# project.net
KiCad netlist of a schematic drawn in EAGLE
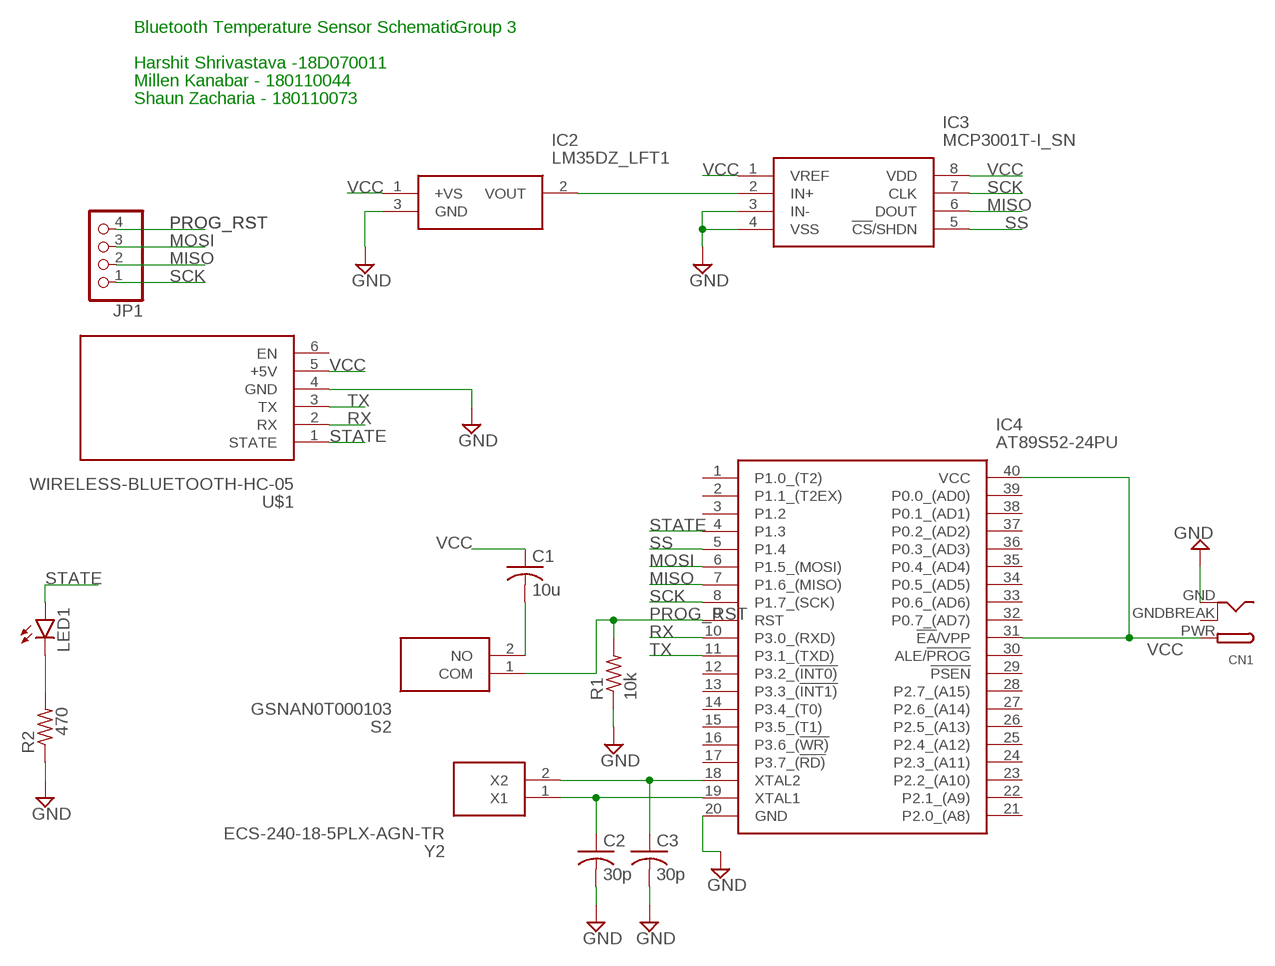
[diagram p0: schematic, sheet 1]

(export (version "E")
  (design (tool "Eeschema 10.0.6"))
  (components
    (comp (ref "C1")
      (value "10u")
      (footprint "eagle-import:C025-050X050")
      (libsource (lib "eagle-import") (part "C-US025-050X050"))
    )
    (comp (ref "C2")
      (value "30p")
      (footprint "eagle-import:C025-050X050")
      (libsource (lib "eagle-import") (part "C-US025-050X050"))
    )
    (comp (ref "C3")
      (value "30p")
      (footprint "eagle-import:C025-050X050")
      (libsource (lib "eagle-import") (part "C-US025-050X050"))
    )
    (comp (ref "CN1")
      (value "DCBARRELPTH")
      (footprint "eagle-import:DCJACK_2MM_PTH")
      (libsource (lib "eagle-import") (part "DCBARRELPTH"))
    )
    (comp (ref "IC2")
      (value "LM35DZ_LFT1")
      (footprint "eagle-import:LP0003A")
      (fields
        (field (name "MANUFACTURER_PART_NUMBER") "LM35DZ/LFT1")
        (field (name "MOUSER_PART_NUMBER") "926-LM35DZ/LFT1")
      )
      (libsource (lib "eagle-import") (part "LM35DZ_LFT1"))
    )
    (comp (ref "IC3")
      (value "MCP3001T-I_SN")
      (footprint "eagle-import:SOIC127P600X175-8N")
      (fields
        (field (name "MANUFACTURER_PART_NUMBER") "MCP3001T-I/SN")
        (field (name "MOUSER_PART_NUMBER") "579-MCP3001T-I/SN")
      )
      (libsource (lib "eagle-import") (part "MCP3001T-I_SN"))
    )
    (comp (ref "IC4")
      (value "AT89S52-24PU")
      (footprint "eagle-import:DIP1556W56P254L5232H483Q40N")
      (fields (field (name "MOUSER_PART_NUMBER") "556-A89S52-24PU"))
      (libsource (lib "eagle-import") (part "AT89S52-24PU"))
    )
    (comp (ref "JP1")
      (value "PINHD-1X4")
      (footprint "eagle-import:1X04")
      (libsource (lib "eagle-import") (part "PINHD-1X4"))
    )
    (comp (ref "LED1")
      (value "LED")
      (footprint "eagle-import:SMARTLED-TTW")
      (libsource (lib "eagle-import") (part "LED"))
    )
    (comp (ref "R1")
      (value "10k")
      (footprint "eagle-import:0207_10")
      (libsource (lib "eagle-import") (part "R-US_0207/10"))
    )
    (comp (ref "R2")
      (value "470")
      (footprint "eagle-import:0207_10")
      (libsource (lib "eagle-import") (part "R-US_0207/10"))
    )
    (comp (ref "S2")
      (value "GSNAN0T000103")
      (footprint "eagle-import:GSNAN0T000103")
      (fields (field (name "MOUSER_PART_NUMBER") "611-GSNAN0T000103"))
      (libsource (lib "eagle-import") (part "GSNAN0T000103"))
    )
    (comp (ref "U$1")
      (value "WIRELESS-BLUETOOTH-HC-05")
      (footprint "eagle-import:WIRELESS-BLUETOOTH-HC-05")
      (libsource (lib "eagle-import") (part "WIRELESS-BLUETOOTH-HC-05"))
    )
    (comp (ref "Y2")
      (value "ECS-240-18-5PLX-AGN-TR")
      (footprint "eagle-import:ECS240185PLXAGNTR")
      (fields (field (name "MOUSER_PART_NUMBER") "520-240-18-5PLXAGNTR"))
      (libsource (lib "eagle-import") (part "ECS-240-18-5PLX-AGN-TR"))
    )
  )
  (nets
    (net (code "1") (name "/GNDBREAK") (class "Default")
      (node (ref "CN1") (pin "GNDBREAK") (pinfunction "GNDBREAK_GNDBREAK") (pintype "power_in"))
    )
    (net (code "2") (name "/MISO") (class "Default")
      (node (ref "IC3") (pin "6") (pinfunction "DOUT_6") (pintype "bidirectional"))
      (node (ref "IC4") (pin "7") (pinfunction "P1.6_(MISO)_7") (pintype "bidirectional"))
      (node (ref "JP1") (pin "2") (pinfunction "2_2") (pintype "passive"))
    )
    (net (code "3") (name "/MOSI") (class "Default")
      (node (ref "IC4") (pin "6") (pinfunction "P1.5_(MOSI)_6") (pintype "bidirectional"))
      (node (ref "JP1") (pin "3") (pinfunction "3_3") (pintype "passive"))
    )
    (net (code "4") (name "/PROG_RST") (class "Default")
      (node (ref "IC4") (pin "9") (pinfunction "RST_9") (pintype "bidirectional"))
      (node (ref "JP1") (pin "4") (pinfunction "4_4") (pintype "passive"))
      (node (ref "R1") (pin "2") (pinfunction "2_2") (pintype "passive"))
      (node (ref "S2") (pin "1") (pinfunction "COM_1") (pintype "bidirectional"))
    )
    (net (code "5") (name "/RX") (class "Default")
      (node (ref "IC4") (pin "10") (pinfunction "P3.0_(RXD)_10") (pintype "bidirectional"))
      (node (ref "U$1") (pin "2") (pinfunction "RX_2") (pintype "bidirectional"))
    )
    (net (code "6") (name "/SCK") (class "Default")
      (node (ref "IC3") (pin "7") (pinfunction "CLK_7") (pintype "bidirectional"))
      (node (ref "IC4") (pin "8") (pinfunction "P1.7_(SCK)_8") (pintype "bidirectional"))
      (node (ref "JP1") (pin "1") (pinfunction "1_1") (pintype "passive"))
    )
    (net (code "7") (name "/SS") (class "Default")
      (node (ref "IC3") (pin "5") (pinfunction "~{CS}/SHDN_5") (pintype "bidirectional"))
      (node (ref "IC4") (pin "5") (pinfunction "P1.4_5") (pintype "bidirectional"))
    )
    (net (code "8") (name "/STATE") (class "Default")
      (node (ref "IC4") (pin "4") (pinfunction "P1.3_4") (pintype "bidirectional"))
      (node (ref "LED1") (pin "A@1") (pinfunction "A_A@1") (pintype "passive"))
      (node (ref "U$1") (pin "1") (pinfunction "STATE_1") (pintype "bidirectional"))
    )
    (net (code "9") (name "/TX") (class "Default")
      (node (ref "IC4") (pin "11") (pinfunction "P3.1_(TXD)_11") (pintype "bidirectional"))
      (node (ref "U$1") (pin "3") (pinfunction "TX_3") (pintype "bidirectional"))
    )
    (net (code "10") (name "/VCC") (class "Default")
      (node (ref "C1") (pin "1") (pinfunction "1_1") (pintype "passive"))
      (node (ref "CN1") (pin "PWR") (pinfunction "PWR_PWR") (pintype "power_in"))
      (node (ref "IC2") (pin "1") (pinfunction "+VS_1") (pintype "bidirectional"))
      (node (ref "IC3") (pin "1") (pinfunction "VREF_1") (pintype "bidirectional"))
      (node (ref "IC3") (pin "8") (pinfunction "VDD_8") (pintype "bidirectional"))
      (node (ref "IC4") (pin "31") (pinfunction "~{EA}/VPP_31") (pintype "bidirectional"))
      (node (ref "IC4") (pin "40") (pinfunction "VCC_40") (pintype "bidirectional"))
      (node (ref "U$1") (pin "5") (pinfunction "+5V_5") (pintype "power_in"))
    )
    (net (code "11") (name "GND") (class "Default")
      (node (ref "C2") (pin "2") (pinfunction "2_2") (pintype "passive"))
      (node (ref "C3") (pin "2") (pinfunction "2_2") (pintype "passive"))
      (node (ref "CN1") (pin "GND") (pinfunction "GND_GND") (pintype "power_in"))
      (node (ref "IC2") (pin "3") (pinfunction "GND_3") (pintype "bidirectional"))
      (node (ref "IC3") (pin "3") (pinfunction "IN-_3") (pintype "bidirectional"))
      (node (ref "IC3") (pin "4") (pinfunction "VSS_4") (pintype "bidirectional"))
      (node (ref "IC4") (pin "20") (pinfunction "GND_20") (pintype "bidirectional"))
      (node (ref "R1") (pin "1") (pinfunction "1_1") (pintype "passive"))
      (node (ref "R2") (pin "1") (pinfunction "1_1") (pintype "passive"))
      (node (ref "U$1") (pin "4") (pinfunction "GND_4") (pintype "power_in"))
    )
    (net (code "12") (name "Net-(IC2-VOUT)") (class "Default")
      (node (ref "IC2") (pin "2") (pinfunction "VOUT_2") (pintype "bidirectional"))
      (node (ref "IC3") (pin "2") (pinfunction "IN+_2") (pintype "bidirectional"))
    )
    (net (code "13") (name "Net-(IC4-XTAL1)") (class "Default")
      (node (ref "C2") (pin "1") (pinfunction "1_1") (pintype "passive"))
      (node (ref "IC4") (pin "19") (pinfunction "XTAL1_19") (pintype "bidirectional"))
      (node (ref "Y2") (pin "1") (pinfunction "X1_1") (pintype "bidirectional"))
    )
    (net (code "14") (name "Net-(IC4-XTAL2)") (class "Default")
      (node (ref "C3") (pin "1") (pinfunction "1_1") (pintype "passive"))
      (node (ref "IC4") (pin "18") (pinfunction "XTAL2_18") (pintype "bidirectional"))
      (node (ref "Y2") (pin "2") (pinfunction "X2_2") (pintype "bidirectional"))
    )
    (net (code "15") (name "Net-(LED1-C)") (class "Default")
      (node (ref "LED1") (pin "C@1") (pinfunction "C_C@1") (pintype "passive"))
      (node (ref "R2") (pin "2") (pinfunction "2_2") (pintype "passive"))
    )
    (net (code "16") (name "Net-(S2-NO)") (class "Default")
      (node (ref "C1") (pin "2") (pinfunction "2_2") (pintype "passive"))
      (node (ref "S2") (pin "2") (pinfunction "NO_2") (pintype "bidirectional"))
    )
    (net (code "17") (name "unconnected-(IC4-ALE{slash}~{PROG}-Pad30)") (class "Default")
      (node (ref "IC4") (pin "30") (pinfunction "ALE/~{PROG}_30") (pintype "bidirectional"))
    )
    (net (code "18") (name "unconnected-(IC4-P0.0_(AD0)-Pad39)") (class "Default")
      (node (ref "IC4") (pin "39") (pinfunction "P0.0_(AD0)_39") (pintype "bidirectional"))
    )
    (net (code "19") (name "unconnected-(IC4-P0.1_(AD1)-Pad38)") (class "Default")
      (node (ref "IC4") (pin "38") (pinfunction "P0.1_(AD1)_38") (pintype "bidirectional"))
    )
    (net (code "20") (name "unconnected-(IC4-P0.2_(AD2)-Pad37)") (class "Default")
      (node (ref "IC4") (pin "37") (pinfunction "P0.2_(AD2)_37") (pintype "bidirectional"))
    )
    (net (code "21") (name "unconnected-(IC4-P0.3_(AD3)-Pad36)") (class "Default")
      (node (ref "IC4") (pin "36") (pinfunction "P0.3_(AD3)_36") (pintype "bidirectional"))
    )
    (net (code "22") (name "unconnected-(IC4-P0.4_(AD4)-Pad35)") (class "Default")
      (node (ref "IC4") (pin "35") (pinfunction "P0.4_(AD4)_35") (pintype "bidirectional"))
    )
    (net (code "23") (name "unconnected-(IC4-P0.5_(AD5)-Pad34)") (class "Default")
      (node (ref "IC4") (pin "34") (pinfunction "P0.5_(AD5)_34") (pintype "bidirectional"))
    )
    (net (code "24") (name "unconnected-(IC4-P0.6_(AD6)-Pad33)") (class "Default")
      (node (ref "IC4") (pin "33") (pinfunction "P0.6_(AD6)_33") (pintype "bidirectional"))
    )
    (net (code "25") (name "unconnected-(IC4-P0.7_(AD7)-Pad32)") (class "Default")
      (node (ref "IC4") (pin "32") (pinfunction "P0.7_(AD7)_32") (pintype "bidirectional"))
    )
    (net (code "26") (name "unconnected-(IC4-P1.0_(T2)-Pad1)") (class "Default")
      (node (ref "IC4") (pin "1") (pinfunction "P1.0_(T2)_1") (pintype "bidirectional"))
    )
    (net (code "27") (name "unconnected-(IC4-P1.1_(T2EX)-Pad2)") (class "Default")
      (node (ref "IC4") (pin "2") (pinfunction "P1.1_(T2EX)_2") (pintype "bidirectional"))
    )
    (net (code "28") (name "unconnected-(IC4-P1.2-Pad3)") (class "Default")
      (node (ref "IC4") (pin "3") (pinfunction "P1.2_3") (pintype "bidirectional"))
    )
    (net (code "29") (name "unconnected-(IC4-P2.0_(A8)-Pad21)") (class "Default")
      (node (ref "IC4") (pin "21") (pinfunction "P2.0_(A8)_21") (pintype "bidirectional"))
    )
    (net (code "30") (name "unconnected-(IC4-P2.1_(A9)-Pad22)") (class "Default")
      (node (ref "IC4") (pin "22") (pinfunction "P2.1_(A9)_22") (pintype "bidirectional"))
    )
    (net (code "31") (name "unconnected-(IC4-P2.2_(A10)-Pad23)") (class "Default")
      (node (ref "IC4") (pin "23") (pinfunction "P2.2_(A10)_23") (pintype "bidirectional"))
    )
    (net (code "32") (name "unconnected-(IC4-P2.3_(A11)-Pad24)") (class "Default")
      (node (ref "IC4") (pin "24") (pinfunction "P2.3_(A11)_24") (pintype "bidirectional"))
    )
    (net (code "33") (name "unconnected-(IC4-P2.4_(A12)-Pad25)") (class "Default")
      (node (ref "IC4") (pin "25") (pinfunction "P2.4_(A12)_25") (pintype "bidirectional"))
    )
    (net (code "34") (name "unconnected-(IC4-P2.5_(A13)-Pad26)") (class "Default")
      (node (ref "IC4") (pin "26") (pinfunction "P2.5_(A13)_26") (pintype "bidirectional"))
    )
    (net (code "35") (name "unconnected-(IC4-P2.6_(A14)-Pad27)") (class "Default")
      (node (ref "IC4") (pin "27") (pinfunction "P2.6_(A14)_27") (pintype "bidirectional"))
    )
    (net (code "36") (name "unconnected-(IC4-P2.7_(A15)-Pad28)") (class "Default")
      (node (ref "IC4") (pin "28") (pinfunction "P2.7_(A15)_28") (pintype "bidirectional"))
    )
    (net (code "37") (name "unconnected-(IC4-P3.2_(~{INT0})-Pad12)") (class "Default")
      (node (ref "IC4") (pin "12") (pinfunction "P3.2_(~{INT0})_12") (pintype "bidirectional"))
    )
    (net (code "38") (name "unconnected-(IC4-P3.3_(~{INT1})-Pad13)") (class "Default")
      (node (ref "IC4") (pin "13") (pinfunction "P3.3_(~{INT1})_13") (pintype "bidirectional"))
    )
    (net (code "39") (name "unconnected-(IC4-P3.4_(T0)-Pad14)") (class "Default")
      (node (ref "IC4") (pin "14") (pinfunction "P3.4_(T0)_14") (pintype "bidirectional"))
    )
    (net (code "40") (name "unconnected-(IC4-P3.5_(T1)-Pad15)") (class "Default")
      (node (ref "IC4") (pin "15") (pinfunction "P3.5_(T1)_15") (pintype "bidirectional"))
    )
    (net (code "41") (name "unconnected-(IC4-P3.6_(~{WR})-Pad16)") (class "Default")
      (node (ref "IC4") (pin "16") (pinfunction "P3.6_(~{WR})_16") (pintype "bidirectional"))
    )
    (net (code "42") (name "unconnected-(IC4-P3.7_(~{RD})-Pad17)") (class "Default")
      (node (ref "IC4") (pin "17") (pinfunction "P3.7_(~{RD})_17") (pintype "bidirectional"))
    )
    (net (code "43") (name "unconnected-(IC4-~{PSEN}-Pad29)") (class "Default")
      (node (ref "IC4") (pin "29") (pinfunction "~{PSEN}_29") (pintype "bidirectional"))
    )
    (net (code "44") (name "unconnected-(U$1-EN-Pad6)") (class "Default")
      (node (ref "U$1") (pin "6") (pinfunction "EN_6") (pintype "bidirectional"))
    )
  )
)
